# MPC23S17-IO-Board.net
KiCad netlist of a schematic drawn in EAGLE
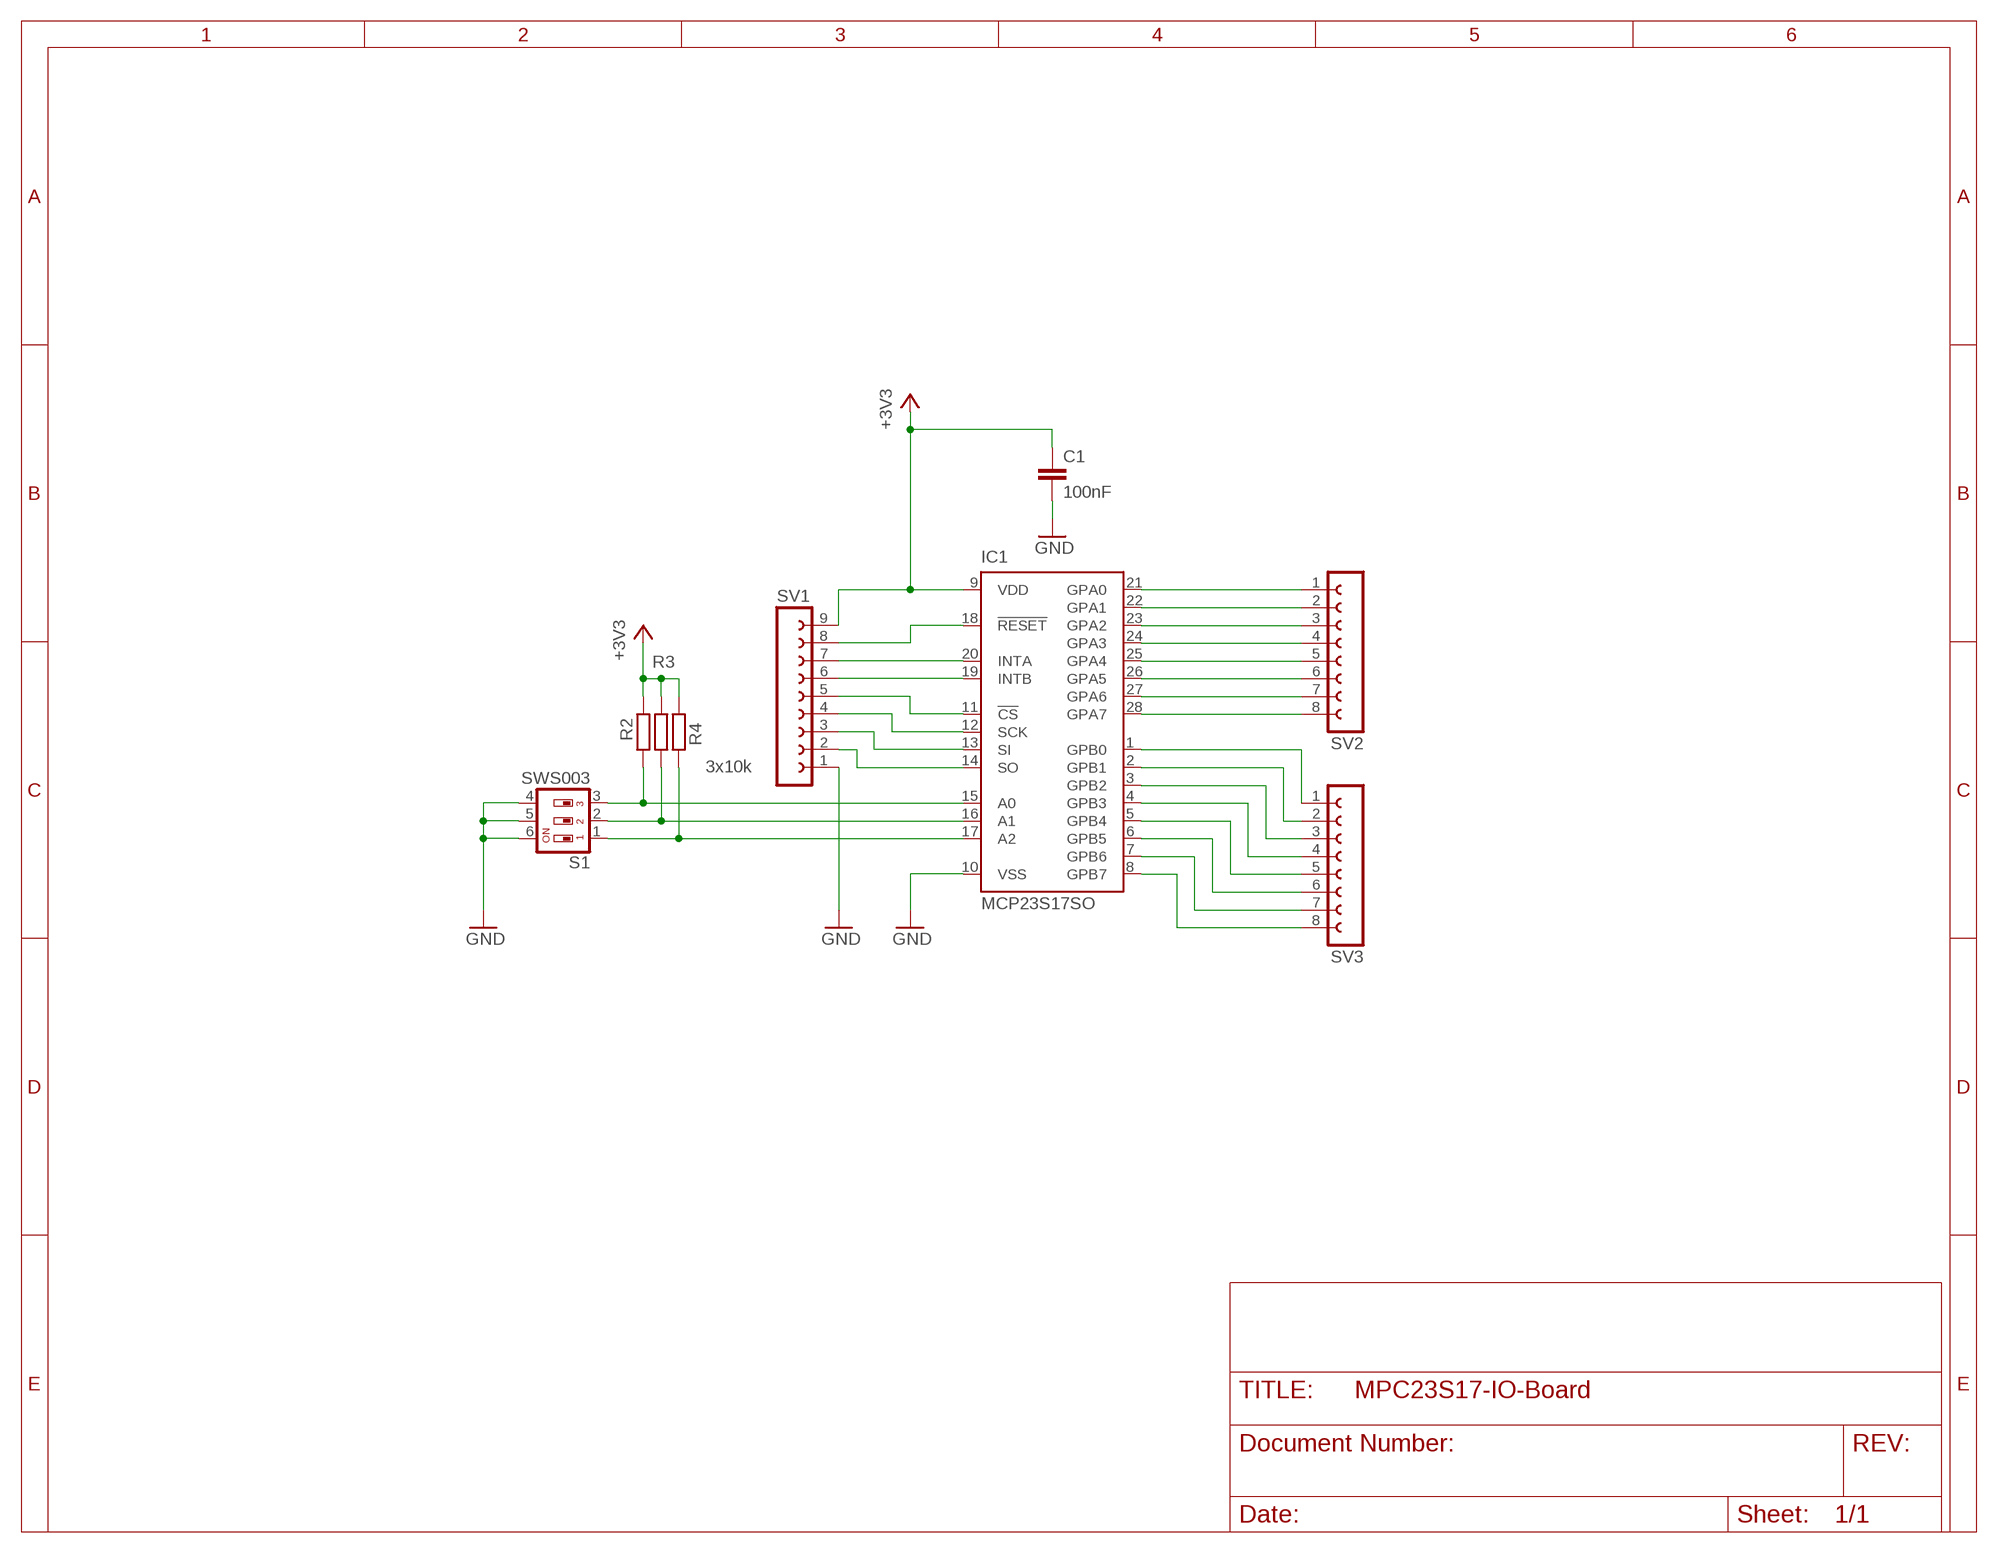
[diagram p0: schematic, sheet 1]

(export (version "E")
  (design (tool "Eeschema 10.0.6"))
  (components
    (comp (ref "C1")
      (value "100nF")
      (footprint "eagle-import:C1206")
      (libsource (lib "eagle-import") (part "C-EUC1206"))
    )
    (comp (ref "IC1")
      (value "MCP23S17SO")
      (footprint "eagle-import:SO28W")
      (libsource (lib "eagle-import") (part "MCP23S17SO"))
    )
    (comp (ref "R2")
      (value "10k")
      (footprint "eagle-import:M1206")
      (libsource (lib "eagle-import") (part "R-EU_M1206"))
    )
    (comp (ref "R3")
      (value "10k")
      (footprint "eagle-import:M1206")
      (libsource (lib "eagle-import") (part "R-EU_M1206"))
    )
    (comp (ref "R4")
      (value "3x10k")
      (footprint "eagle-import:M1206")
      (libsource (lib "eagle-import") (part "R-EU_M1206"))
    )
    (comp (ref "S1")
      (value "SWS003")
      (footprint "eagle-import:SMS-003")
      (libsource (lib "eagle-import") (part "SWS003"))
    )
    (comp (ref "SV1")
      (value "FE09-1")
      (footprint "eagle-import:FE09")
      (libsource (lib "eagle-import") (part "FE09-1"))
    )
    (comp (ref "SV2")
      (value "FE08-1")
      (footprint "eagle-import:FE08")
      (libsource (lib "eagle-import") (part "FE08-1"))
    )
    (comp (ref "SV3")
      (value "FE08-1")
      (footprint "eagle-import:FE08")
      (libsource (lib "eagle-import") (part "FE08-1"))
    )
  )
  (nets
    (net (code "1") (name "+3V3") (class "Default")
      (node (ref "C1") (pin "1") (pinfunction "1_1") (pintype "passive"))
      (node (ref "IC1") (pin "9") (pinfunction "VDD_9") (pintype "power_in"))
      (node (ref "R2") (pin "1") (pinfunction "1_1") (pintype "passive"))
      (node (ref "R3") (pin "1") (pinfunction "1_1") (pintype "passive"))
      (node (ref "R4") (pin "1") (pinfunction "1_1") (pintype "passive"))
      (node (ref "SV1") (pin "9") (pinfunction "9_9") (pintype "passive"))
    )
    (net (code "2") (name "GND") (class "Default")
      (node (ref "C1") (pin "2") (pinfunction "2_2") (pintype "passive"))
      (node (ref "IC1") (pin "10") (pinfunction "VSS_10") (pintype "power_in"))
      (node (ref "S1") (pin "4") (pinfunction "4_4") (pintype "passive"))
      (node (ref "S1") (pin "5") (pinfunction "5_5") (pintype "passive"))
      (node (ref "S1") (pin "6") (pinfunction "6_6") (pintype "passive"))
      (node (ref "SV1") (pin "1") (pinfunction "1_1") (pintype "passive"))
    )
    (net (code "3") (name "Net-(IC1-A0)") (class "Default")
      (node (ref "IC1") (pin "15") (pinfunction "A0_15") (pintype "input"))
      (node (ref "R2") (pin "2") (pinfunction "2_2") (pintype "passive"))
      (node (ref "S1") (pin "3") (pinfunction "3_3") (pintype "passive"))
    )
    (net (code "4") (name "Net-(IC1-A1)") (class "Default")
      (node (ref "IC1") (pin "16") (pinfunction "A1_16") (pintype "input"))
      (node (ref "R3") (pin "2") (pinfunction "2_2") (pintype "passive"))
      (node (ref "S1") (pin "2") (pinfunction "2_2") (pintype "passive"))
    )
    (net (code "5") (name "Net-(IC1-A2)") (class "Default")
      (node (ref "IC1") (pin "17") (pinfunction "A2_17") (pintype "input"))
      (node (ref "R4") (pin "2") (pinfunction "2_2") (pintype "passive"))
      (node (ref "S1") (pin "1") (pinfunction "1_1") (pintype "passive"))
    )
    (net (code "6") (name "Net-(IC1-GPA0)") (class "Default")
      (node (ref "IC1") (pin "21") (pinfunction "GPA0_21") (pintype "bidirectional"))
      (node (ref "SV2") (pin "1") (pinfunction "1_1") (pintype "passive"))
    )
    (net (code "7") (name "Net-(IC1-GPA1)") (class "Default")
      (node (ref "IC1") (pin "22") (pinfunction "GPA1_22") (pintype "bidirectional"))
      (node (ref "SV2") (pin "2") (pinfunction "2_2") (pintype "passive"))
    )
    (net (code "8") (name "Net-(IC1-GPA2)") (class "Default")
      (node (ref "IC1") (pin "23") (pinfunction "GPA2_23") (pintype "bidirectional"))
      (node (ref "SV2") (pin "3") (pinfunction "3_3") (pintype "passive"))
    )
    (net (code "9") (name "Net-(IC1-GPA3)") (class "Default")
      (node (ref "IC1") (pin "24") (pinfunction "GPA3_24") (pintype "bidirectional"))
      (node (ref "SV2") (pin "4") (pinfunction "4_4") (pintype "passive"))
    )
    (net (code "10") (name "Net-(IC1-GPA4)") (class "Default")
      (node (ref "IC1") (pin "25") (pinfunction "GPA4_25") (pintype "bidirectional"))
      (node (ref "SV2") (pin "5") (pinfunction "5_5") (pintype "passive"))
    )
    (net (code "11") (name "Net-(IC1-GPA5)") (class "Default")
      (node (ref "IC1") (pin "26") (pinfunction "GPA5_26") (pintype "bidirectional"))
      (node (ref "SV2") (pin "6") (pinfunction "6_6") (pintype "passive"))
    )
    (net (code "12") (name "Net-(IC1-GPA6)") (class "Default")
      (node (ref "IC1") (pin "27") (pinfunction "GPA6_27") (pintype "bidirectional"))
      (node (ref "SV2") (pin "7") (pinfunction "7_7") (pintype "passive"))
    )
    (net (code "13") (name "Net-(IC1-GPA7)") (class "Default")
      (node (ref "IC1") (pin "28") (pinfunction "GPA7_28") (pintype "bidirectional"))
      (node (ref "SV2") (pin "8") (pinfunction "8_8") (pintype "passive"))
    )
    (net (code "14") (name "Net-(IC1-GPB0)") (class "Default")
      (node (ref "IC1") (pin "1") (pinfunction "GPB0_1") (pintype "bidirectional"))
      (node (ref "SV3") (pin "1") (pinfunction "1_1") (pintype "passive"))
    )
    (net (code "15") (name "Net-(IC1-GPB1)") (class "Default")
      (node (ref "IC1") (pin "2") (pinfunction "GPB1_2") (pintype "bidirectional"))
      (node (ref "SV3") (pin "2") (pinfunction "2_2") (pintype "passive"))
    )
    (net (code "16") (name "Net-(IC1-GPB2)") (class "Default")
      (node (ref "IC1") (pin "3") (pinfunction "GPB2_3") (pintype "bidirectional"))
      (node (ref "SV3") (pin "3") (pinfunction "3_3") (pintype "passive"))
    )
    (net (code "17") (name "Net-(IC1-GPB3)") (class "Default")
      (node (ref "IC1") (pin "4") (pinfunction "GPB3_4") (pintype "bidirectional"))
      (node (ref "SV3") (pin "4") (pinfunction "4_4") (pintype "passive"))
    )
    (net (code "18") (name "Net-(IC1-GPB4)") (class "Default")
      (node (ref "IC1") (pin "5") (pinfunction "GPB4_5") (pintype "bidirectional"))
      (node (ref "SV3") (pin "5") (pinfunction "5_5") (pintype "passive"))
    )
    (net (code "19") (name "Net-(IC1-GPB5)") (class "Default")
      (node (ref "IC1") (pin "6") (pinfunction "GPB5_6") (pintype "bidirectional"))
      (node (ref "SV3") (pin "6") (pinfunction "6_6") (pintype "passive"))
    )
    (net (code "20") (name "Net-(IC1-GPB6)") (class "Default")
      (node (ref "IC1") (pin "7") (pinfunction "GPB6_7") (pintype "bidirectional"))
      (node (ref "SV3") (pin "7") (pinfunction "7_7") (pintype "passive"))
    )
    (net (code "21") (name "Net-(IC1-GPB7)") (class "Default")
      (node (ref "IC1") (pin "8") (pinfunction "GPB7_8") (pintype "bidirectional"))
      (node (ref "SV3") (pin "8") (pinfunction "8_8") (pintype "passive"))
    )
    (net (code "22") (name "Net-(IC1-INTA)") (class "Default")
      (node (ref "IC1") (pin "20") (pinfunction "INTA_20") (pintype "output"))
      (node (ref "SV1") (pin "7") (pinfunction "7_7") (pintype "passive"))
    )
    (net (code "23") (name "Net-(IC1-INTB)") (class "Default")
      (node (ref "IC1") (pin "19") (pinfunction "INTB_19") (pintype "output"))
      (node (ref "SV1") (pin "6") (pinfunction "6_6") (pintype "passive"))
    )
    (net (code "24") (name "Net-(IC1-SCK)") (class "Default")
      (node (ref "IC1") (pin "12") (pinfunction "SCK_12") (pintype "input"))
      (node (ref "SV1") (pin "4") (pinfunction "4_4") (pintype "passive"))
    )
    (net (code "25") (name "Net-(IC1-SI)") (class "Default")
      (node (ref "IC1") (pin "13") (pinfunction "SI_13") (pintype "input"))
      (node (ref "SV1") (pin "3") (pinfunction "3_3") (pintype "passive"))
    )
    (net (code "26") (name "Net-(IC1-SO)") (class "Default")
      (node (ref "IC1") (pin "14") (pinfunction "SO_14") (pintype "output"))
      (node (ref "SV1") (pin "2") (pinfunction "2_2") (pintype "passive"))
    )
    (net (code "27") (name "Net-(IC1-~{CS})") (class "Default")
      (node (ref "IC1") (pin "11") (pinfunction "~{CS}_11") (pintype "input"))
      (node (ref "SV1") (pin "5") (pinfunction "5_5") (pintype "passive"))
    )
    (net (code "28") (name "Net-(IC1-~{RESET})") (class "Default")
      (node (ref "IC1") (pin "18") (pinfunction "~{RESET}_18") (pintype "input"))
      (node (ref "SV1") (pin "8") (pinfunction "8_8") (pintype "passive"))
    )
  )
)
